# MyFirstSch.net
KiCad netlist of a schematic drawn in Altium Designer
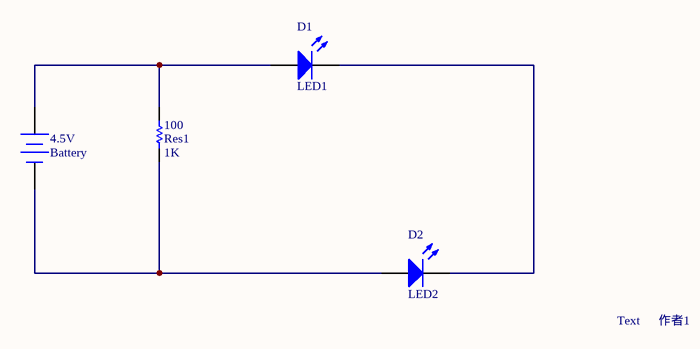
[diagram p0: MyFirstSch.SchDoc]

(export (version "E")
  (design (tool "Eeschema 10.0.6"))
  (components
    (comp (ref "4.5V")
      (value "Battery")
      (footprint "BAT-2")
      (description "Multicell Battery")
      (fields (field (name "PUBLISHER") "Altium Limited"))
      (libsource (lib "Miscellaneous Devices") (part "Battery"))
    )
    (comp (ref "100")
      (value "Res1")
      (footprint "AXIAL-0.3")
      (description "Resistor")
      (fields (field (name "ALTIUM_VALUE") "1K") (field (name "PUBLISHER") "Altium Limited"))
      (libsource (lib "Miscellaneous Devices") (part "Res1"))
    )
    (comp (ref "D1")
      (value "LED1")
      (footprint "3.2X1.6X1.1")
      (description "Typical RED, GREEN, YELLOW, AMBER GaAs LED")
      (fields (field (name "PUBLISHER") "Altium Limited"))
      (libsource (lib "Miscellaneous Devices") (part "LED2"))
    )
    (comp (ref "D2")
      (value "LED2")
      (footprint "3.2X1.6X1.1")
      (description "Typical RED, GREEN, YELLOW, AMBER GaAs LED")
      (fields (field (name "PUBLISHER") "Altium Limited"))
      (libsource (lib "Miscellaneous Devices") (part "LED2"))
    )
  )
  (nets
    (net (code "1") (name "Net-(4.5V-+)") (class "Default")
      (node (ref "100") (pin "1") (pinfunction "1_1") (pintype "passive"))
      (node (ref "4.5V") (pin "1") (pinfunction "+_1") (pintype "passive"))
      (node (ref "D1") (pin "1") (pinfunction "A_1") (pintype "passive"))
    )
    (net (code "2") (name "Net-(4.5V--)") (class "Default")
      (node (ref "100") (pin "2") (pinfunction "2_2") (pintype "passive"))
      (node (ref "4.5V") (pin "2") (pinfunction "-_2") (pintype "passive"))
      (node (ref "D2") (pin "1") (pinfunction "A_1") (pintype "passive"))
    )
    (net (code "3") (name "Net-(D1-K)") (class "Default")
      (node (ref "D1") (pin "2") (pinfunction "K_2") (pintype "passive"))
      (node (ref "D2") (pin "2") (pinfunction "K_2") (pintype "passive"))
    )
  )
)
